# Output_buffer_A_and_B_Page_2.net
KiCad netlist of a schematic drawn in Altium Designer
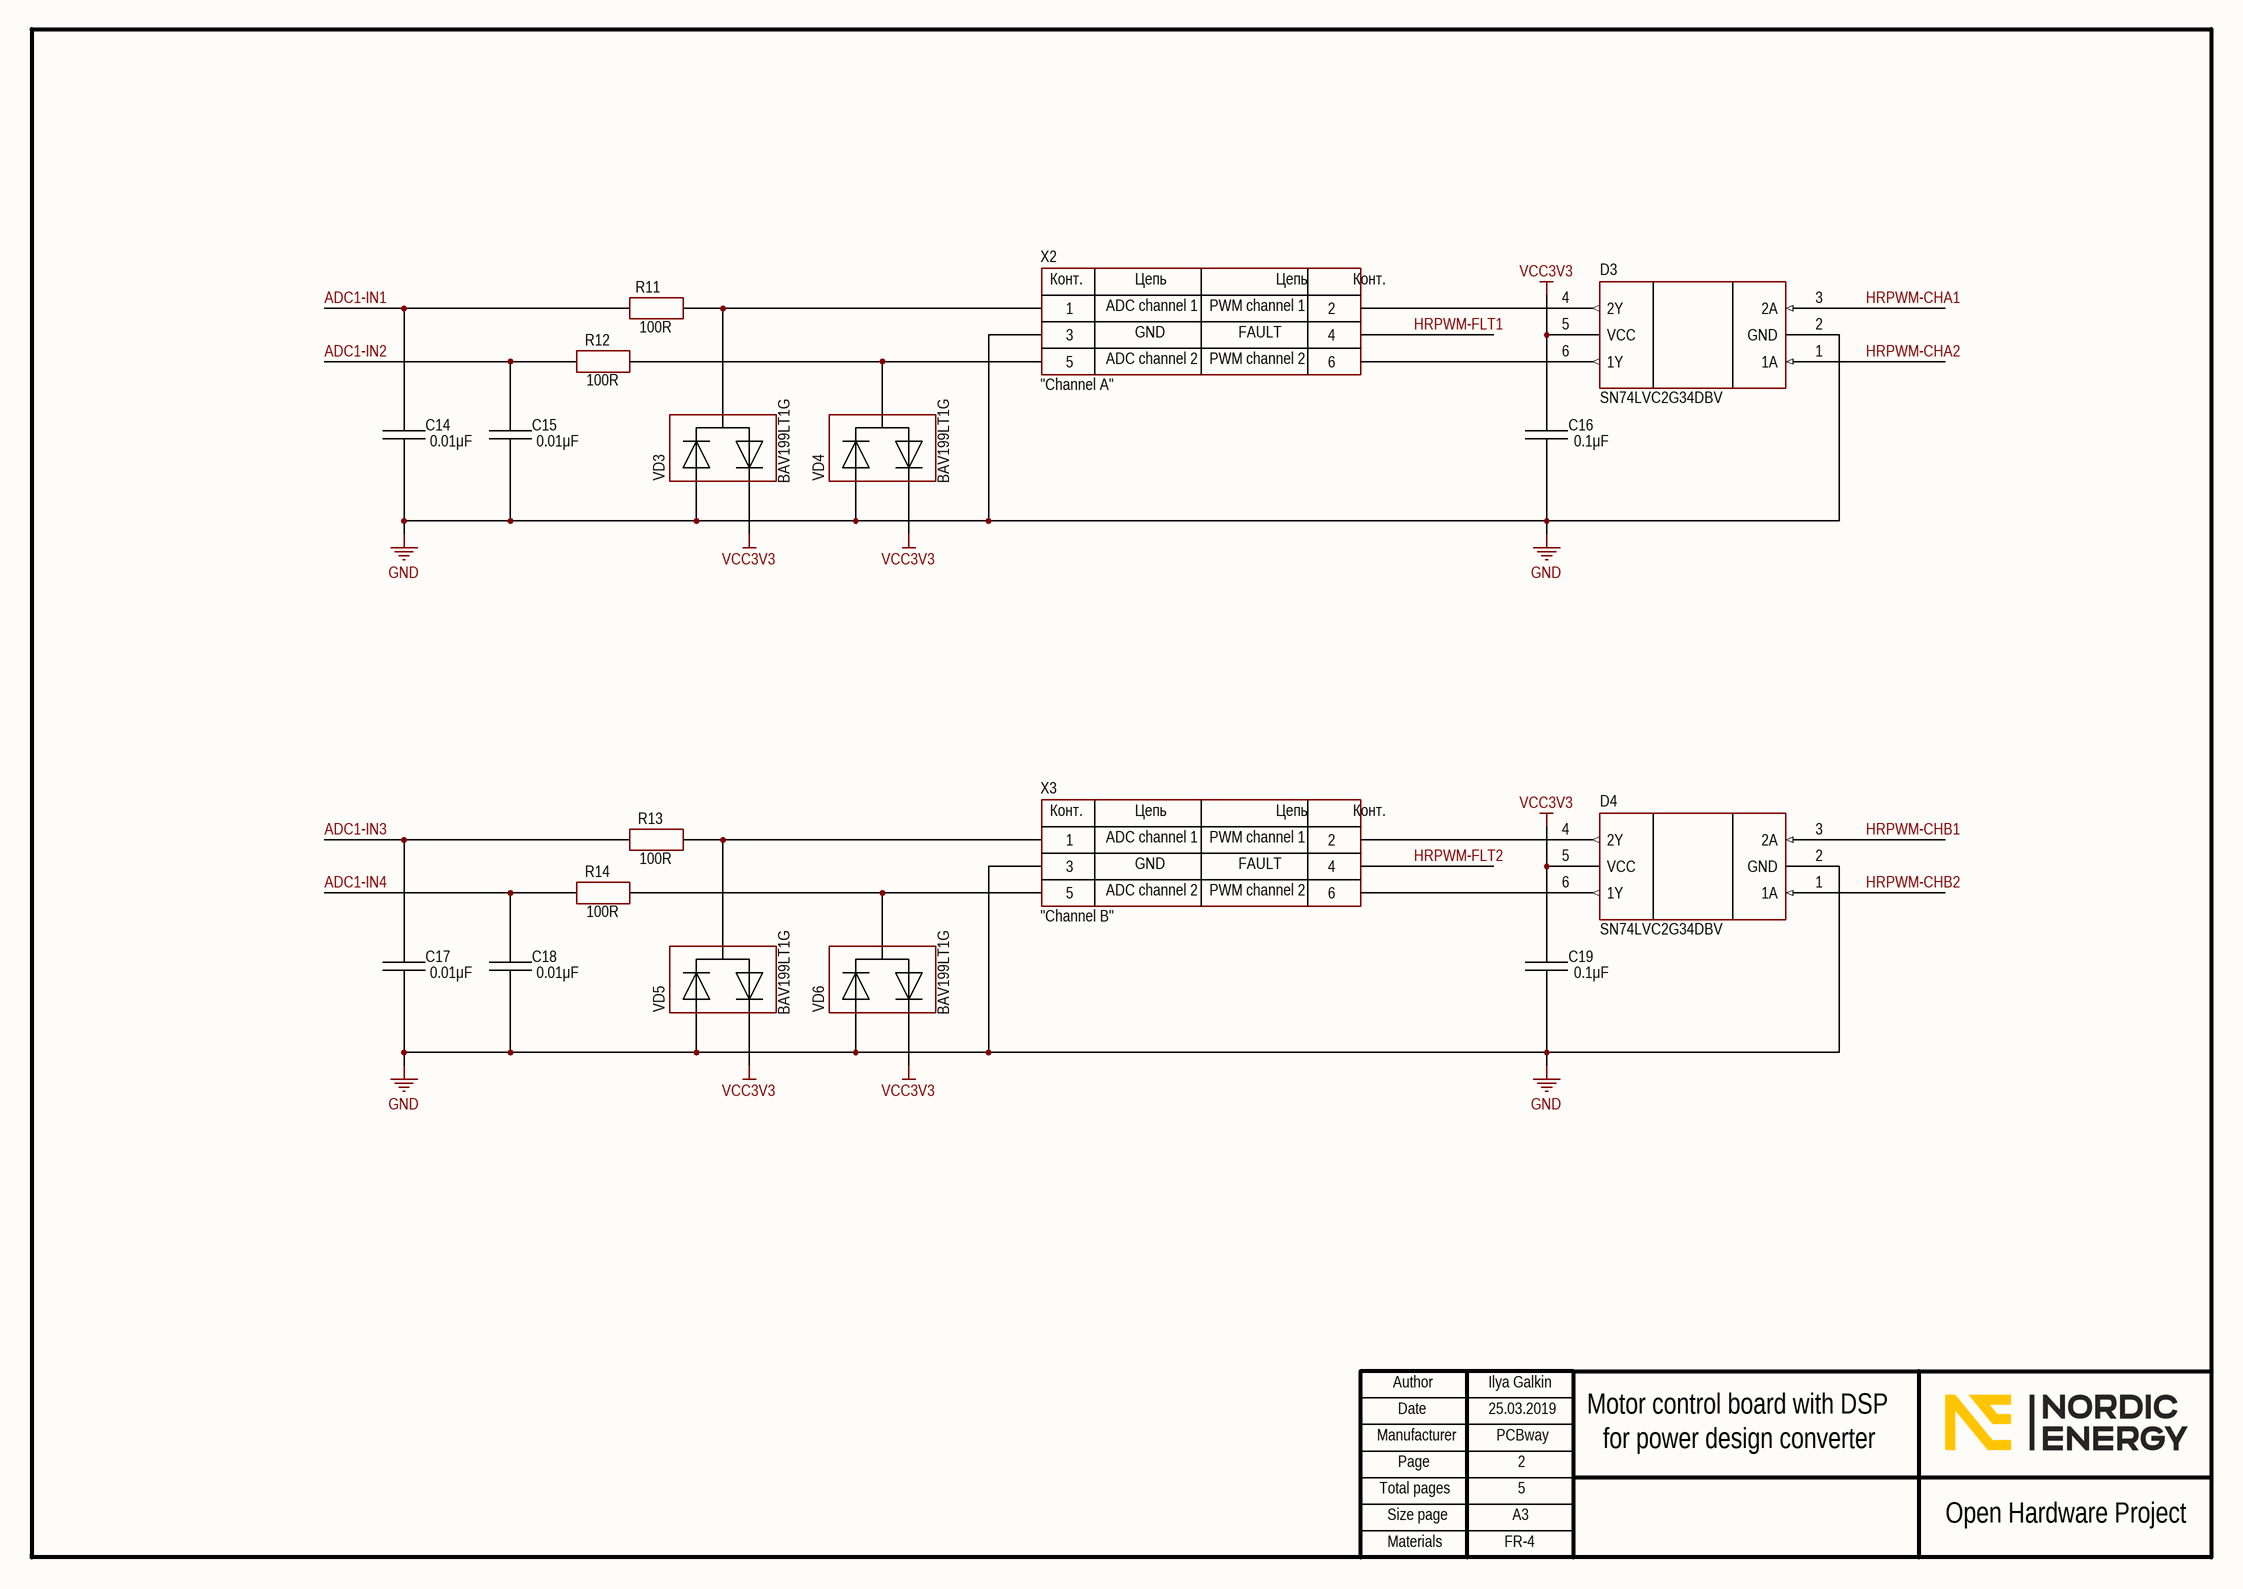
[diagram p0: Output buffer A and B. Page 2.SchDoc]

(export (version "E")
  (design (tool "Eeschema 10.0.6"))
  (components
    (comp (ref "C14")
      (value "0.01μF")
      (footprint "CH0805C")
      (fields (field (name "MANUFACTURER") "Yageo"))
      (libsource (lib "Discrete") (part "Capacitor"))
    )
    (comp (ref "C15")
      (value "0.01μF")
      (footprint "CH0805C")
      (fields (field (name "MANUFACTURER") "Yageo"))
      (libsource (lib "Discrete") (part "Capacitor"))
    )
    (comp (ref "C16")
      (value "0.1μF")
      (footprint "CH0805C")
      (fields (field (name "MANUFACTURER") "Yageo"))
      (libsource (lib "Discrete") (part "Capacitor"))
    )
    (comp (ref "C17")
      (value "0.01μF")
      (footprint "CH0805C")
      (fields (field (name "MANUFACTURER") "Yageo"))
      (libsource (lib "Discrete") (part "Capacitor"))
    )
    (comp (ref "C18")
      (value "0.01μF")
      (footprint "CH0805C")
      (fields (field (name "MANUFACTURER") "Yageo"))
      (libsource (lib "Discrete") (part "Capacitor"))
    )
    (comp (ref "C19")
      (value "0.1μF")
      (footprint "CH0805C")
      (fields (field (name "MANUFACTURER") "Yageo"))
      (libsource (lib "Discrete") (part "Capacitor"))
    )
    (comp (ref "D3")
      (value "SN74LVC2G34DBV")
      (footprint "SOT23-6")
      (description "Buffer")
      (fields (field (name "MANUFACTURER") "Texas Instruments"))
      (libsource (lib "Analog") (part "SN74LVC2G34DBV"))
    )
    (comp (ref "D4")
      (value "SN74LVC2G34DBV")
      (footprint "SOT23-6")
      (description "Buffer")
      (fields (field (name "MANUFACTURER") "Texas Instruments"))
      (libsource (lib "Analog") (part "SN74LVC2G34DBV"))
    )
    (comp (ref "R11")
      (value "100R")
      (footprint "CH0805R")
      (fields (field (name "MANUFACTURER") "Yageo"))
      (libsource (lib "Discrete") (part "Resistor"))
    )
    (comp (ref "R12")
      (value "100R")
      (footprint "CH0805R")
      (fields (field (name "MANUFACTURER") "Yageo"))
      (libsource (lib "Discrete") (part "Resistor"))
    )
    (comp (ref "R13")
      (value "100R")
      (footprint "CH0805R")
      (fields (field (name "MANUFACTURER") "Yageo"))
      (libsource (lib "Discrete") (part "Resistor"))
    )
    (comp (ref "R14")
      (value "100R")
      (footprint "CH0805R")
      (fields (field (name "MANUFACTURER") "Yageo"))
      (libsource (lib "Discrete") (part "Resistor"))
    )
    (comp (ref "VD3")
      (value "BAV199LT1G")
      (footprint "SOT23_132")
      (fields (field (name "MANUFACTURER") "ON Semiconductor"))
      (libsource (lib "Diods") (part "Diod Array"))
    )
    (comp (ref "VD4")
      (value "BAV199LT1G")
      (footprint "SOT23_132")
      (fields (field (name "MANUFACTURER") "ON Semiconductor"))
      (libsource (lib "Diods") (part "Diod Array"))
    )
    (comp (ref "VD5")
      (value "BAV199LT1G")
      (footprint "SOT23_132")
      (fields (field (name "MANUFACTURER") "ON Semiconductor"))
      (libsource (lib "Diods") (part "Diod Array"))
    )
    (comp (ref "VD6")
      (value "BAV199LT1G")
      (footprint "SOT23_132")
      (fields (field (name "MANUFACTURER") "ON Semiconductor"))
      (libsource (lib "Diods") (part "Diod Array"))
    )
    (comp (ref "X2")
      (value "\"Channel A\"")
      (footprint "CON: PLD-6")
      (libsource (lib "Connectors") (part "6(2)-Connector"))
    )
    (comp (ref "X3")
      (value "\"Channel B\"")
      (footprint "CON: PLD-6")
      (libsource (lib "Connectors") (part "6(2)-Connector"))
    )
  )
  (nets
    (net (code "1") (name "/ADC1-IN1") (class "Default")
      (node (ref "C14") (pin "2") (pinfunction "2_2") (pintype "power_in"))
      (node (ref "R11") (pin "1") (pinfunction "1_1") (pintype "passive"))
    )
    (net (code "2") (name "/ADC1-IN2") (class "Default")
      (node (ref "C15") (pin "2") (pinfunction "2_2") (pintype "power_in"))
      (node (ref "R12") (pin "1") (pinfunction "1_1") (pintype "passive"))
    )
    (net (code "3") (name "/ADC1-IN3") (class "Default")
      (node (ref "C17") (pin "2") (pinfunction "2_2") (pintype "power_in"))
      (node (ref "R13") (pin "1") (pinfunction "1_1") (pintype "passive"))
    )
    (net (code "4") (name "/ADC1-IN4") (class "Default")
      (node (ref "C18") (pin "2") (pinfunction "2_2") (pintype "power_in"))
      (node (ref "R14") (pin "1") (pinfunction "1_1") (pintype "passive"))
    )
    (net (code "5") (name "/HRPWM-CHA1") (class "Default")
      (node (ref "D3") (pin "3") (pinfunction "2A_3") (pintype "input"))
    )
    (net (code "6") (name "/HRPWM-CHA2") (class "Default")
      (node (ref "D3") (pin "1") (pinfunction "1A_1") (pintype "input"))
    )
    (net (code "7") (name "/HRPWM-CHB1") (class "Default")
      (node (ref "D4") (pin "3") (pinfunction "2A_3") (pintype "input"))
    )
    (net (code "8") (name "/HRPWM-CHB2") (class "Default")
      (node (ref "D4") (pin "1") (pinfunction "1A_1") (pintype "input"))
    )
    (net (code "9") (name "/HRPWM-FLT1") (class "Default")
      (node (ref "X2") (pin "4") (pinfunction "4_4") (pintype "passive"))
    )
    (net (code "10") (name "/HRPWM-FLT2") (class "Default")
      (node (ref "X3") (pin "4") (pinfunction "4_4") (pintype "passive"))
    )
    (net (code "11") (name "GND") (class "Default")
      (node (ref "C14") (pin "1") (pinfunction "1_1") (pintype "power_in"))
      (node (ref "C15") (pin "1") (pinfunction "1_1") (pintype "power_in"))
      (node (ref "C16") (pin "1") (pinfunction "1_1") (pintype "power_in"))
      (node (ref "C17") (pin "1") (pinfunction "1_1") (pintype "power_in"))
      (node (ref "C18") (pin "1") (pinfunction "1_1") (pintype "power_in"))
      (node (ref "C19") (pin "1") (pinfunction "1_1") (pintype "power_in"))
      (node (ref "D3") (pin "2") (pinfunction "GND_2") (pintype "passive"))
      (node (ref "D4") (pin "2") (pinfunction "GND_2") (pintype "passive"))
      (node (ref "VD3") (pin "1") (pinfunction "1_1") (pintype "passive"))
      (node (ref "VD4") (pin "1") (pinfunction "1_1") (pintype "passive"))
      (node (ref "VD5") (pin "1") (pinfunction "1_1") (pintype "passive"))
      (node (ref "VD6") (pin "1") (pinfunction "1_1") (pintype "passive"))
      (node (ref "X2") (pin "3") (pinfunction "3_3") (pintype "passive"))
      (node (ref "X3") (pin "3") (pinfunction "3_3") (pintype "passive"))
    )
    (net (code "12") (name "Net-(D3-1Y)") (class "Default")
      (node (ref "D3") (pin "6") (pinfunction "1Y_6") (pintype "output"))
      (node (ref "X2") (pin "6") (pinfunction "6_6") (pintype "power_in"))
    )
    (net (code "13") (name "Net-(D3-2Y)") (class "Default")
      (node (ref "D3") (pin "4") (pinfunction "2Y_4") (pintype "output"))
      (node (ref "X2") (pin "2") (pinfunction "2_2") (pintype "passive"))
    )
    (net (code "14") (name "Net-(D4-1Y)") (class "Default")
      (node (ref "D4") (pin "6") (pinfunction "1Y_6") (pintype "output"))
      (node (ref "X3") (pin "6") (pinfunction "6_6") (pintype "power_in"))
    )
    (net (code "15") (name "Net-(D4-2Y)") (class "Default")
      (node (ref "D4") (pin "4") (pinfunction "2Y_4") (pintype "output"))
      (node (ref "X3") (pin "2") (pinfunction "2_2") (pintype "passive"))
    )
    (net (code "16") (name "Net-(R11-Pad2)") (class "Default")
      (node (ref "R11") (pin "2") (pinfunction "2_2") (pintype "passive"))
      (node (ref "VD3") (pin "3") (pinfunction "3_3") (pintype "passive"))
      (node (ref "X2") (pin "1") (pinfunction "1_1") (pintype "passive"))
    )
    (net (code "17") (name "Net-(R12-Pad2)") (class "Default")
      (node (ref "R12") (pin "2") (pinfunction "2_2") (pintype "passive"))
      (node (ref "VD4") (pin "3") (pinfunction "3_3") (pintype "passive"))
      (node (ref "X2") (pin "5") (pinfunction "5_5") (pintype "power_in"))
    )
    (net (code "18") (name "Net-(R13-Pad2)") (class "Default")
      (node (ref "R13") (pin "2") (pinfunction "2_2") (pintype "passive"))
      (node (ref "VD5") (pin "3") (pinfunction "3_3") (pintype "passive"))
      (node (ref "X3") (pin "1") (pinfunction "1_1") (pintype "passive"))
    )
    (net (code "19") (name "Net-(R14-Pad2)") (class "Default")
      (node (ref "R14") (pin "2") (pinfunction "2_2") (pintype "passive"))
      (node (ref "VD6") (pin "3") (pinfunction "3_3") (pintype "passive"))
      (node (ref "X3") (pin "5") (pinfunction "5_5") (pintype "power_in"))
    )
    (net (code "20") (name "VCC3V3") (class "Default")
      (node (ref "C16") (pin "2") (pinfunction "2_2") (pintype "power_in"))
      (node (ref "C19") (pin "2") (pinfunction "2_2") (pintype "power_in"))
      (node (ref "D3") (pin "5") (pinfunction "VCC_5") (pintype "passive"))
      (node (ref "D4") (pin "5") (pinfunction "VCC_5") (pintype "passive"))
      (node (ref "VD3") (pin "2") (pinfunction "2_2") (pintype "passive"))
      (node (ref "VD4") (pin "2") (pinfunction "2_2") (pintype "passive"))
      (node (ref "VD5") (pin "2") (pinfunction "2_2") (pintype "passive"))
      (node (ref "VD6") (pin "2") (pinfunction "2_2") (pintype "passive"))
    )
  )
)
